# Teensy3.net
KiCad netlist of a schematic drawn in EAGLE
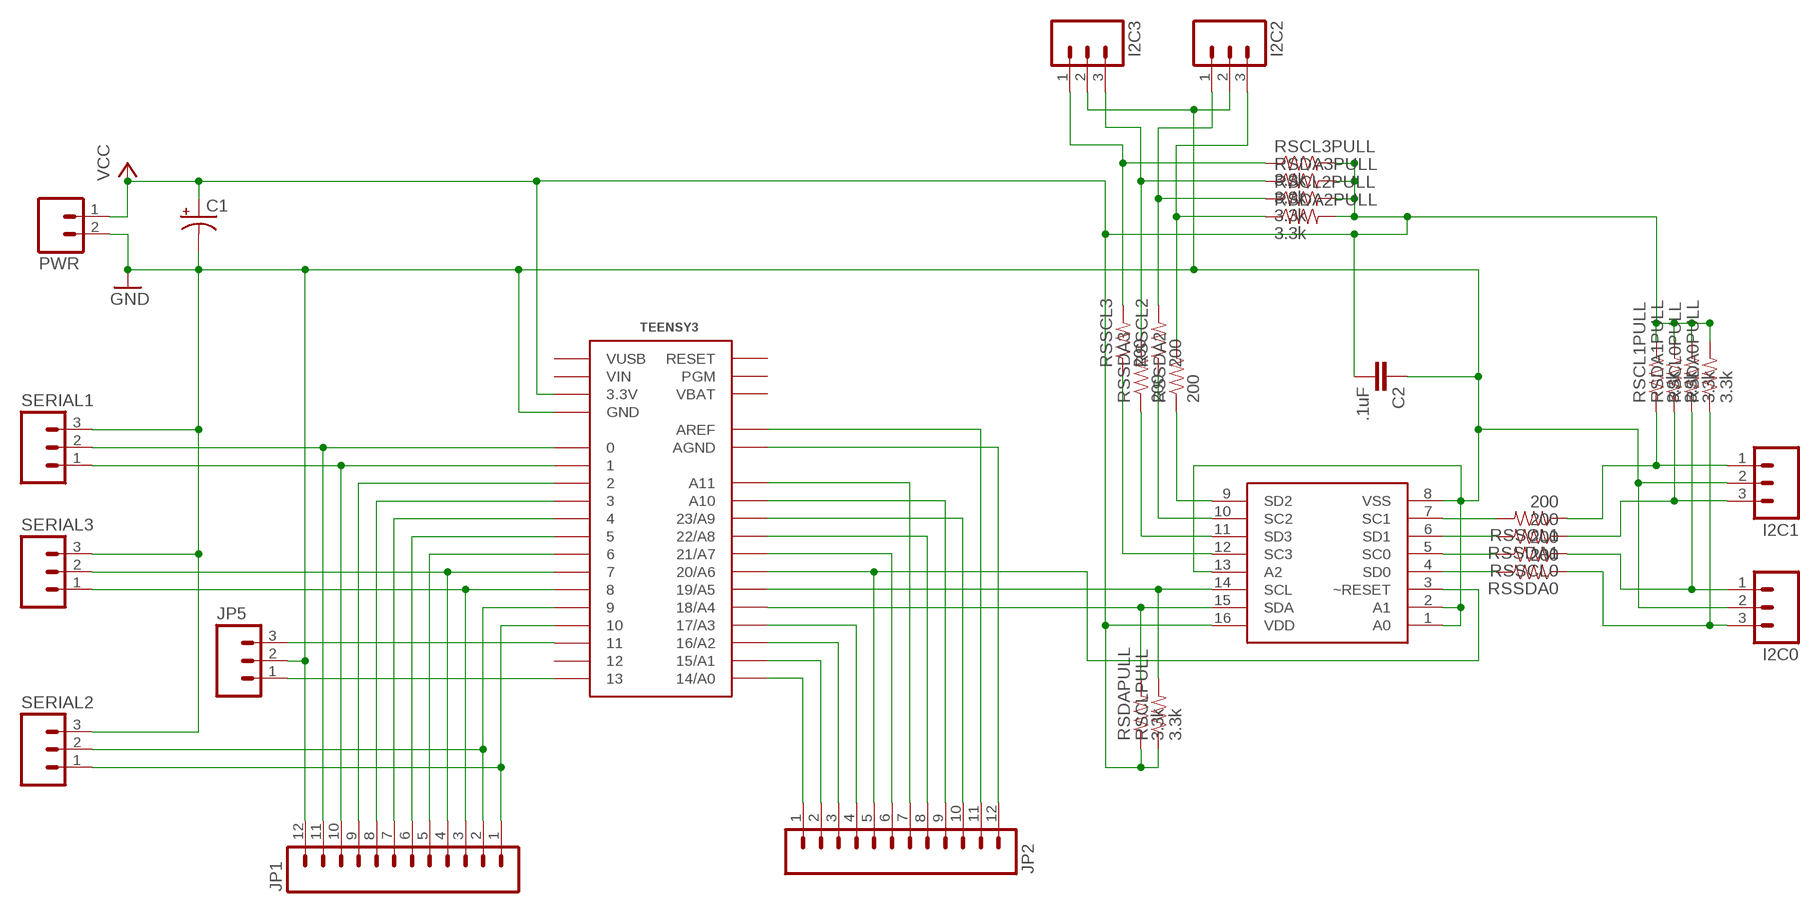
[diagram p0: schematic, sheet 1]

(export (version "E")
  (design (tool "Eeschema 10.0.6"))
  (components
    (comp (ref "C1")
      (value "CAP_POLPTH1")
      (footprint "eagle-import:CPOL-RADIAL-100UF-25V")
      (libsource (lib "eagle-import") (part "CAP_POLPTH1"))
    )
    (comp (ref "C2")
      (value ".1uF")
      (footprint "eagle-import:0805")
      (libsource (lib "eagle-import") (part "CAP0805"))
    )
    (comp (ref "I2C0")
      (value "M03SCREW")
      (footprint "eagle-import:SCREWTERMINAL-3.5MM-3")
      (libsource (lib "eagle-import") (part "M03SCREW"))
    )
    (comp (ref "I2C1")
      (value "M03SCREW")
      (footprint "eagle-import:SCREWTERMINAL-3.5MM-3")
      (libsource (lib "eagle-import") (part "M03SCREW"))
    )
    (comp (ref "I2C2")
      (value "M03SCREW")
      (footprint "eagle-import:SCREWTERMINAL-3.5MM-3")
      (libsource (lib "eagle-import") (part "M03SCREW"))
    )
    (comp (ref "I2C3")
      (value "M03SCREW")
      (footprint "eagle-import:SCREWTERMINAL-3.5MM-3")
      (libsource (lib "eagle-import") (part "M03SCREW"))
    )
    (comp (ref "IC1")
      (value "PCA9646SO16")
      (footprint "eagle-import:SO16")
      (libsource (lib "eagle-import") (part "PCA9646SO16"))
    )
    (comp (ref "JP1")
      (value "M12LOCK")
      (footprint "eagle-import:1X12_LOCK")
      (libsource (lib "eagle-import") (part "M12LOCK"))
    )
    (comp (ref "JP2")
      (value "M12LOCK")
      (footprint "eagle-import:1X12_LOCK")
      (libsource (lib "eagle-import") (part "M12LOCK"))
    )
    (comp (ref "JP5")
      (value "M03SCREW")
      (footprint "eagle-import:SCREWTERMINAL-3.5MM-3")
      (libsource (lib "eagle-import") (part "M03SCREW"))
    )
    (comp (ref "PWR")
      (value "M02POLAR_LOCK")
      (footprint "eagle-import:MOLEX-1X2_LOCK")
      (libsource (lib "eagle-import") (part "M02POLAR_LOCK"))
    )
    (comp (ref "RSCL0PULL")
      (value "3.3k")
      (footprint "eagle-import:0603-RES")
      (libsource (lib "eagle-import") (part "RESISTOR0603-RES"))
    )
    (comp (ref "RSCL1PULL")
      (value "3.3k")
      (footprint "eagle-import:0603-RES")
      (libsource (lib "eagle-import") (part "RESISTOR0603-RES"))
    )
    (comp (ref "RSCL2PULL")
      (value "3.3k")
      (footprint "eagle-import:0603-RES")
      (libsource (lib "eagle-import") (part "RESISTOR0603-RES"))
    )
    (comp (ref "RSCL3PULL")
      (value "3.3k")
      (footprint "eagle-import:0603-RES")
      (libsource (lib "eagle-import") (part "RESISTOR0603-RES"))
    )
    (comp (ref "RSCLPULL")
      (value "3.3k")
      (footprint "eagle-import:0603-RES")
      (libsource (lib "eagle-import") (part "RESISTOR0603-RES"))
    )
    (comp (ref "RSDA0PULL")
      (value "3.3k")
      (footprint "eagle-import:0603-RES")
      (libsource (lib "eagle-import") (part "RESISTOR0603-RES"))
    )
    (comp (ref "RSDA1PULL")
      (value "3.3k")
      (footprint "eagle-import:0603-RES")
      (libsource (lib "eagle-import") (part "RESISTOR0603-RES"))
    )
    (comp (ref "RSDA2PULL")
      (value "3.3k")
      (footprint "eagle-import:0603-RES")
      (libsource (lib "eagle-import") (part "RESISTOR0603-RES"))
    )
    (comp (ref "RSDA3PULL")
      (value "3.3k")
      (footprint "eagle-import:0603-RES")
      (libsource (lib "eagle-import") (part "RESISTOR0603-RES"))
    )
    (comp (ref "RSDAPULL")
      (value "3.3k")
      (footprint "eagle-import:0603-RES")
      (libsource (lib "eagle-import") (part "RESISTOR0603-RES"))
    )
    (comp (ref "RSSCL0")
      (value "200")
      (footprint "eagle-import:0603-RES")
      (libsource (lib "eagle-import") (part "RESISTOR0603-RES"))
    )
    (comp (ref "RSSCL1")
      (value "200")
      (footprint "eagle-import:0603-RES")
      (libsource (lib "eagle-import") (part "RESISTOR0603-RES"))
    )
    (comp (ref "RSSCL2")
      (value "200")
      (footprint "eagle-import:0603-RES")
      (libsource (lib "eagle-import") (part "RESISTOR0603-RES"))
    )
    (comp (ref "RSSCL3")
      (value "200")
      (footprint "eagle-import:0603-RES")
      (libsource (lib "eagle-import") (part "RESISTOR0603-RES"))
    )
    (comp (ref "RSSDA0")
      (value "200")
      (footprint "eagle-import:0603-RES")
      (libsource (lib "eagle-import") (part "RESISTOR0603-RES"))
    )
    (comp (ref "RSSDA1")
      (value "200")
      (footprint "eagle-import:0603-RES")
      (libsource (lib "eagle-import") (part "RESISTOR0603-RES"))
    )
    (comp (ref "RSSDA2")
      (value "200")
      (footprint "eagle-import:0603-RES")
      (libsource (lib "eagle-import") (part "RESISTOR0603-RES"))
    )
    (comp (ref "RSSDA3")
      (value "200")
      (footprint "eagle-import:0603-RES")
      (libsource (lib "eagle-import") (part "RESISTOR0603-RES"))
    )
    (comp (ref "SERIAL1")
      (value "M03LOCK")
      (footprint "eagle-import:1X03_LOCK")
      (libsource (lib "eagle-import") (part "M03LOCK"))
    )
    (comp (ref "SERIAL2")
      (value "M03LOCK")
      (footprint "eagle-import:1X03_LOCK")
      (libsource (lib "eagle-import") (part "M03LOCK"))
    )
    (comp (ref "SERIAL3")
      (value "M03LOCK")
      (footprint "eagle-import:1X03_LOCK")
      (libsource (lib "eagle-import") (part "M03LOCK"))
    )
    (comp (ref "TEENSY3")
      (value "TEENSY_3.0+4")
      (footprint "eagle-import:TEENSY_3.0+4")
      (libsource (lib "eagle-import") (part "TEENSY_3.0+4"))
    )
  )
  (nets
    (net (code "1") (name "/VBAT") (class "Default")
      (node (ref "TEENSY3") (pin "VBAT") (pinfunction "VBAT_VBAT") (pintype "power_in"))
    )
    (net (code "2") (name "/VIN") (class "Default")
      (node (ref "TEENSY3") (pin "VIN") (pinfunction "VIN_VIN") (pintype "power_in"))
    )
    (net (code "3") (name "/VUSB") (class "Default")
      (node (ref "TEENSY3") (pin "VUSB") (pinfunction "VUSB_VUSB") (pintype "power_in"))
    )
    (net (code "4") (name "GND") (class "Default")
      (node (ref "C1") (pin "2") (pinfunction "-_2") (pintype "passive"))
      (node (ref "C2") (pin "1") (pinfunction "1_1") (pintype "passive"))
      (node (ref "I2C0") (pin "2") (pinfunction "2_2") (pintype "passive"))
      (node (ref "I2C1") (pin "2") (pinfunction "2_2") (pintype "passive"))
      (node (ref "I2C2") (pin "2") (pinfunction "2_2") (pintype "passive"))
      (node (ref "I2C3") (pin "2") (pinfunction "2_2") (pintype "passive"))
      (node (ref "IC1") (pin "1") (pinfunction "A0_1") (pintype "input"))
      (node (ref "IC1") (pin "13") (pinfunction "A2_13") (pintype "input"))
      (node (ref "IC1") (pin "2") (pinfunction "A1_2") (pintype "input"))
      (node (ref "IC1") (pin "8") (pinfunction "VSS_8") (pintype "power_in"))
      (node (ref "JP1") (pin "12") (pinfunction "12_12") (pintype "passive"))
      (node (ref "JP5") (pin "2") (pinfunction "2_2") (pintype "passive"))
      (node (ref "PWR") (pin "2") (pinfunction "2_2") (pintype "passive"))
      (node (ref "SERIAL1") (pin "3") (pinfunction "3_3") (pintype "passive"))
      (node (ref "SERIAL2") (pin "3") (pinfunction "3_3") (pintype "passive"))
      (node (ref "SERIAL3") (pin "3") (pinfunction "3_3") (pintype "passive"))
      (node (ref "TEENSY3") (pin "GND") (pinfunction "GND_GND") (pintype "power_in"))
      (node (ref "TEENSY3") (pin "GND1") (pinfunction "GND_GND1") (pintype "power_in"))
    )
    (net (code "5") (name "Net-(I2C0-Pad1)") (class "Default")
      (node (ref "I2C0") (pin "1") (pinfunction "1_1") (pintype "passive"))
      (node (ref "RSCL0PULL") (pin "1") (pinfunction "1_1") (pintype "passive"))
      (node (ref "RSSCL0") (pin "1") (pinfunction "1_1") (pintype "passive"))
    )
    (net (code "6") (name "Net-(I2C0-Pad3)") (class "Default")
      (node (ref "I2C0") (pin "3") (pinfunction "3_3") (pintype "passive"))
      (node (ref "RSDA0PULL") (pin "1") (pinfunction "1_1") (pintype "passive"))
      (node (ref "RSSDA0") (pin "1") (pinfunction "1_1") (pintype "passive"))
    )
    (net (code "7") (name "Net-(I2C1-Pad1)") (class "Default")
      (node (ref "I2C1") (pin "1") (pinfunction "1_1") (pintype "passive"))
      (node (ref "RSCL1PULL") (pin "1") (pinfunction "1_1") (pintype "passive"))
      (node (ref "RSSCL1") (pin "1") (pinfunction "1_1") (pintype "passive"))
    )
    (net (code "8") (name "Net-(I2C1-Pad3)") (class "Default")
      (node (ref "I2C1") (pin "3") (pinfunction "3_3") (pintype "passive"))
      (node (ref "RSDA1PULL") (pin "1") (pinfunction "1_1") (pintype "passive"))
      (node (ref "RSSDA1") (pin "1") (pinfunction "1_1") (pintype "passive"))
    )
    (net (code "9") (name "Net-(I2C2-Pad1)") (class "Default")
      (node (ref "I2C2") (pin "1") (pinfunction "1_1") (pintype "passive"))
      (node (ref "RSCL2PULL") (pin "1") (pinfunction "1_1") (pintype "passive"))
      (node (ref "RSSCL2") (pin "2") (pinfunction "2_2") (pintype "passive"))
    )
    (net (code "10") (name "Net-(I2C2-Pad3)") (class "Default")
      (node (ref "I2C2") (pin "3") (pinfunction "3_3") (pintype "passive"))
      (node (ref "RSDA2PULL") (pin "1") (pinfunction "1_1") (pintype "passive"))
      (node (ref "RSSDA2") (pin "2") (pinfunction "2_2") (pintype "passive"))
    )
    (net (code "11") (name "Net-(I2C3-Pad1)") (class "Default")
      (node (ref "I2C3") (pin "1") (pinfunction "1_1") (pintype "passive"))
      (node (ref "RSCL3PULL") (pin "1") (pinfunction "1_1") (pintype "passive"))
      (node (ref "RSSCL3") (pin "2") (pinfunction "2_2") (pintype "passive"))
    )
    (net (code "12") (name "Net-(I2C3-Pad3)") (class "Default")
      (node (ref "I2C3") (pin "3") (pinfunction "3_3") (pintype "passive"))
      (node (ref "RSDA3PULL") (pin "1") (pinfunction "1_1") (pintype "passive"))
      (node (ref "RSSDA3") (pin "2") (pinfunction "2_2") (pintype "passive"))
    )
    (net (code "13") (name "Net-(IC1-SC0)") (class "Default")
      (node (ref "IC1") (pin "5") (pinfunction "SC0_5") (pintype "output"))
      (node (ref "RSSCL0") (pin "2") (pinfunction "2_2") (pintype "passive"))
    )
    (net (code "14") (name "Net-(IC1-SC1)") (class "Default")
      (node (ref "IC1") (pin "7") (pinfunction "SC1_7") (pintype "output"))
      (node (ref "RSSCL1") (pin "2") (pinfunction "2_2") (pintype "passive"))
    )
    (net (code "15") (name "Net-(IC1-SC2)") (class "Default")
      (node (ref "IC1") (pin "10") (pinfunction "SC2_10") (pintype "output"))
      (node (ref "RSSCL2") (pin "1") (pinfunction "1_1") (pintype "passive"))
    )
    (net (code "16") (name "Net-(IC1-SC3)") (class "Default")
      (node (ref "IC1") (pin "12") (pinfunction "SC3_12") (pintype "output"))
      (node (ref "RSSCL3") (pin "1") (pinfunction "1_1") (pintype "passive"))
    )
    (net (code "17") (name "Net-(IC1-SCL)") (class "Default")
      (node (ref "IC1") (pin "14") (pinfunction "SCL_14") (pintype "input"))
      (node (ref "RSCLPULL") (pin "2") (pinfunction "2_2") (pintype "passive"))
      (node (ref "TEENSY3") (pin "19/A5") (pinfunction "19/A5_19/A5") (pintype "bidirectional"))
    )
    (net (code "18") (name "Net-(IC1-SD0)") (class "Default")
      (node (ref "IC1") (pin "4") (pinfunction "SD0_4") (pintype "bidirectional"))
      (node (ref "RSSDA0") (pin "2") (pinfunction "2_2") (pintype "passive"))
    )
    (net (code "19") (name "Net-(IC1-SD1)") (class "Default")
      (node (ref "IC1") (pin "6") (pinfunction "SD1_6") (pintype "bidirectional"))
      (node (ref "RSSDA1") (pin "2") (pinfunction "2_2") (pintype "passive"))
    )
    (net (code "20") (name "Net-(IC1-SD2)") (class "Default")
      (node (ref "IC1") (pin "9") (pinfunction "SD2_9") (pintype "bidirectional"))
      (node (ref "RSSDA2") (pin "1") (pinfunction "1_1") (pintype "passive"))
    )
    (net (code "21") (name "Net-(IC1-SD3)") (class "Default")
      (node (ref "IC1") (pin "11") (pinfunction "SD3_11") (pintype "bidirectional"))
      (node (ref "RSSDA3") (pin "1") (pinfunction "1_1") (pintype "passive"))
    )
    (net (code "22") (name "Net-(IC1-SDA)") (class "Default")
      (node (ref "IC1") (pin "15") (pinfunction "SDA_15") (pintype "bidirectional"))
      (node (ref "RSDAPULL") (pin "2") (pinfunction "2_2") (pintype "passive"))
      (node (ref "TEENSY3") (pin "18/A4") (pinfunction "18/A4_18/A4") (pintype "bidirectional"))
    )
    (net (code "23") (name "Net-(IC1-~{RESET})") (class "Default")
      (node (ref "IC1") (pin "3") (pinfunction "~{RESET}_3") (pintype "input"))
      (node (ref "JP2") (pin "5") (pinfunction "5_5") (pintype "passive"))
      (node (ref "TEENSY3") (pin "20/A6") (pinfunction "20/A6_20/A6") (pintype "bidirectional"))
    )
    (net (code "24") (name "Net-(JP1-Pad1)") (class "Default")
      (node (ref "JP1") (pin "1") (pinfunction "1_1") (pintype "passive"))
      (node (ref "SERIAL2") (pin "1") (pinfunction "1_1") (pintype "passive"))
      (node (ref "TEENSY3") (pin "10") (pinfunction "10_10") (pintype "bidirectional"))
    )
    (net (code "25") (name "Net-(JP1-Pad2)") (class "Default")
      (node (ref "JP1") (pin "2") (pinfunction "2_2") (pintype "passive"))
      (node (ref "SERIAL2") (pin "2") (pinfunction "2_2") (pintype "passive"))
      (node (ref "TEENSY3") (pin "9") (pinfunction "9_9") (pintype "bidirectional"))
    )
    (net (code "26") (name "Net-(JP1-Pad3)") (class "Default")
      (node (ref "JP1") (pin "3") (pinfunction "3_3") (pintype "passive"))
      (node (ref "SERIAL3") (pin "1") (pinfunction "1_1") (pintype "passive"))
      (node (ref "TEENSY3") (pin "8") (pinfunction "8_8") (pintype "bidirectional"))
    )
    (net (code "27") (name "Net-(JP1-Pad4)") (class "Default")
      (node (ref "JP1") (pin "4") (pinfunction "4_4") (pintype "passive"))
      (node (ref "SERIAL3") (pin "2") (pinfunction "2_2") (pintype "passive"))
      (node (ref "TEENSY3") (pin "7") (pinfunction "7_7") (pintype "bidirectional"))
    )
    (net (code "28") (name "Net-(JP1-Pad5)") (class "Default")
      (node (ref "JP1") (pin "5") (pinfunction "5_5") (pintype "passive"))
      (node (ref "TEENSY3") (pin "6") (pinfunction "6_6") (pintype "bidirectional"))
    )
    (net (code "29") (name "Net-(JP1-Pad6)") (class "Default")
      (node (ref "JP1") (pin "6") (pinfunction "6_6") (pintype "passive"))
      (node (ref "TEENSY3") (pin "5") (pinfunction "5_5") (pintype "bidirectional"))
    )
    (net (code "30") (name "Net-(JP1-Pad7)") (class "Default")
      (node (ref "JP1") (pin "7") (pinfunction "7_7") (pintype "passive"))
      (node (ref "TEENSY3") (pin "4") (pinfunction "4_4") (pintype "bidirectional"))
    )
    (net (code "31") (name "Net-(JP1-Pad8)") (class "Default")
      (node (ref "JP1") (pin "8") (pinfunction "8_8") (pintype "passive"))
      (node (ref "TEENSY3") (pin "3") (pinfunction "3_3") (pintype "bidirectional"))
    )
    (net (code "32") (name "Net-(JP1-Pad9)") (class "Default")
      (node (ref "JP1") (pin "9") (pinfunction "9_9") (pintype "passive"))
      (node (ref "TEENSY3") (pin "2") (pinfunction "2_2") (pintype "bidirectional"))
    )
    (net (code "33") (name "Net-(JP1-Pad10)") (class "Default")
      (node (ref "JP1") (pin "10") (pinfunction "10_10") (pintype "passive"))
      (node (ref "SERIAL1") (pin "1") (pinfunction "1_1") (pintype "passive"))
      (node (ref "TEENSY3") (pin "1") (pinfunction "1_1") (pintype "bidirectional"))
    )
    (net (code "34") (name "Net-(JP1-Pad11)") (class "Default")
      (node (ref "JP1") (pin "11") (pinfunction "11_11") (pintype "passive"))
      (node (ref "SERIAL1") (pin "2") (pinfunction "2_2") (pintype "passive"))
      (node (ref "TEENSY3") (pin "0") (pinfunction "0_0") (pintype "bidirectional"))
    )
    (net (code "35") (name "Net-(JP2-Pad1)") (class "Default")
      (node (ref "JP2") (pin "1") (pinfunction "1_1") (pintype "passive"))
      (node (ref "TEENSY3") (pin "14/A0") (pinfunction "14/A0_14/A0") (pintype "bidirectional"))
    )
    (net (code "36") (name "Net-(JP2-Pad2)") (class "Default")
      (node (ref "JP2") (pin "2") (pinfunction "2_2") (pintype "passive"))
      (node (ref "TEENSY3") (pin "15/A1") (pinfunction "15/A1_15/A1") (pintype "bidirectional"))
    )
    (net (code "37") (name "Net-(JP2-Pad3)") (class "Default")
      (node (ref "JP2") (pin "3") (pinfunction "3_3") (pintype "passive"))
      (node (ref "TEENSY3") (pin "16/A2") (pinfunction "16/A2_16/A2") (pintype "bidirectional"))
    )
    (net (code "38") (name "Net-(JP2-Pad4)") (class "Default")
      (node (ref "JP2") (pin "4") (pinfunction "4_4") (pintype "passive"))
      (node (ref "TEENSY3") (pin "17/A3") (pinfunction "17/A3_17/A3") (pintype "bidirectional"))
    )
    (net (code "39") (name "Net-(JP2-Pad6)") (class "Default")
      (node (ref "JP2") (pin "6") (pinfunction "6_6") (pintype "passive"))
      (node (ref "TEENSY3") (pin "21/A7") (pinfunction "21/A7_21/A7") (pintype "bidirectional"))
    )
    (net (code "40") (name "Net-(JP2-Pad7)") (class "Default")
      (node (ref "JP2") (pin "7") (pinfunction "7_7") (pintype "passive"))
      (node (ref "TEENSY3") (pin "A11") (pinfunction "A11_A11") (pintype "bidirectional"))
    )
    (net (code "41") (name "Net-(JP2-Pad8)") (class "Default")
      (node (ref "JP2") (pin "8") (pinfunction "8_8") (pintype "passive"))
      (node (ref "TEENSY3") (pin "22/A8") (pinfunction "22/A8_22/A8") (pintype "bidirectional"))
    )
    (net (code "42") (name "Net-(JP2-Pad9)") (class "Default")
      (node (ref "JP2") (pin "9") (pinfunction "9_9") (pintype "passive"))
      (node (ref "TEENSY3") (pin "A10") (pinfunction "A10_A10") (pintype "bidirectional"))
    )
    (net (code "43") (name "Net-(JP2-Pad10)") (class "Default")
      (node (ref "JP2") (pin "10") (pinfunction "10_10") (pintype "passive"))
      (node (ref "TEENSY3") (pin "23/A9") (pinfunction "23/A9_23/A9") (pintype "bidirectional"))
    )
    (net (code "44") (name "Net-(JP2-Pad11)") (class "Default")
      (node (ref "JP2") (pin "11") (pinfunction "11_11") (pintype "passive"))
      (node (ref "TEENSY3") (pin "AREF") (pinfunction "AREF_AREF") (pintype "power_in"))
    )
    (net (code "45") (name "Net-(JP2-Pad12)") (class "Default")
      (node (ref "JP2") (pin "12") (pinfunction "12_12") (pintype "passive"))
      (node (ref "TEENSY3") (pin "AGND") (pinfunction "AGND_AGND") (pintype "power_in"))
    )
    (net (code "46") (name "Net-(JP5-Pad1)") (class "Default")
      (node (ref "JP5") (pin "1") (pinfunction "1_1") (pintype "passive"))
      (node (ref "TEENSY3") (pin "13") (pinfunction "13_13") (pintype "bidirectional"))
    )
    (net (code "47") (name "Net-(JP5-Pad3)") (class "Default")
      (node (ref "JP5") (pin "3") (pinfunction "3_3") (pintype "passive"))
      (node (ref "TEENSY3") (pin "11") (pinfunction "11_11") (pintype "bidirectional"))
    )
    (net (code "48") (name "VCC") (class "Default")
      (node (ref "C1") (pin "1") (pinfunction "+_1") (pintype "passive"))
      (node (ref "C2") (pin "2") (pinfunction "2_2") (pintype "passive"))
      (node (ref "IC1") (pin "16") (pinfunction "VDD_16") (pintype "power_in"))
      (node (ref "PWR") (pin "1") (pinfunction "1_1") (pintype "passive"))
      (node (ref "RSCL0PULL") (pin "2") (pinfunction "2_2") (pintype "passive"))
      (node (ref "RSCL1PULL") (pin "2") (pinfunction "2_2") (pintype "passive"))
      (node (ref "RSCL2PULL") (pin "2") (pinfunction "2_2") (pintype "passive"))
      (node (ref "RSCL3PULL") (pin "2") (pinfunction "2_2") (pintype "passive"))
      (node (ref "RSCLPULL") (pin "1") (pinfunction "1_1") (pintype "passive"))
      (node (ref "RSDA0PULL") (pin "2") (pinfunction "2_2") (pintype "passive"))
      (node (ref "RSDA1PULL") (pin "2") (pinfunction "2_2") (pintype "passive"))
      (node (ref "RSDA2PULL") (pin "2") (pinfunction "2_2") (pintype "passive"))
      (node (ref "RSDA3PULL") (pin "2") (pinfunction "2_2") (pintype "passive"))
      (node (ref "RSDAPULL") (pin "1") (pinfunction "1_1") (pintype "passive"))
      (node (ref "TEENSY3") (pin "3.3V") (pinfunction "3.3V_3.3V") (pintype "power_in"))
      (node (ref "TEENSY3") (pin "3.3V1") (pinfunction "3.3V_3.3V1") (pintype "power_in"))
    )
    (net (code "49") (name "unconnected-(TEENSY3-Pad12)") (class "Default")
      (node (ref "TEENSY3") (pin "12") (pinfunction "12_12") (pintype "bidirectional"))
    )
    (net (code "50") (name "unconnected-(TEENSY3-PadPGM)") (class "Default")
      (node (ref "TEENSY3") (pin "PGM") (pinfunction "PGM_PGM") (pintype "bidirectional"))
    )
    (net (code "51") (name "unconnected-(TEENSY3-PadRESET)") (class "Default")
      (node (ref "TEENSY3") (pin "RESET") (pinfunction "RESET_RESET") (pintype "bidirectional"))
    )
  )
)
